# SparkFun_ACS712_Breakout_v11.net
KiCad netlist of a schematic drawn in EAGLE
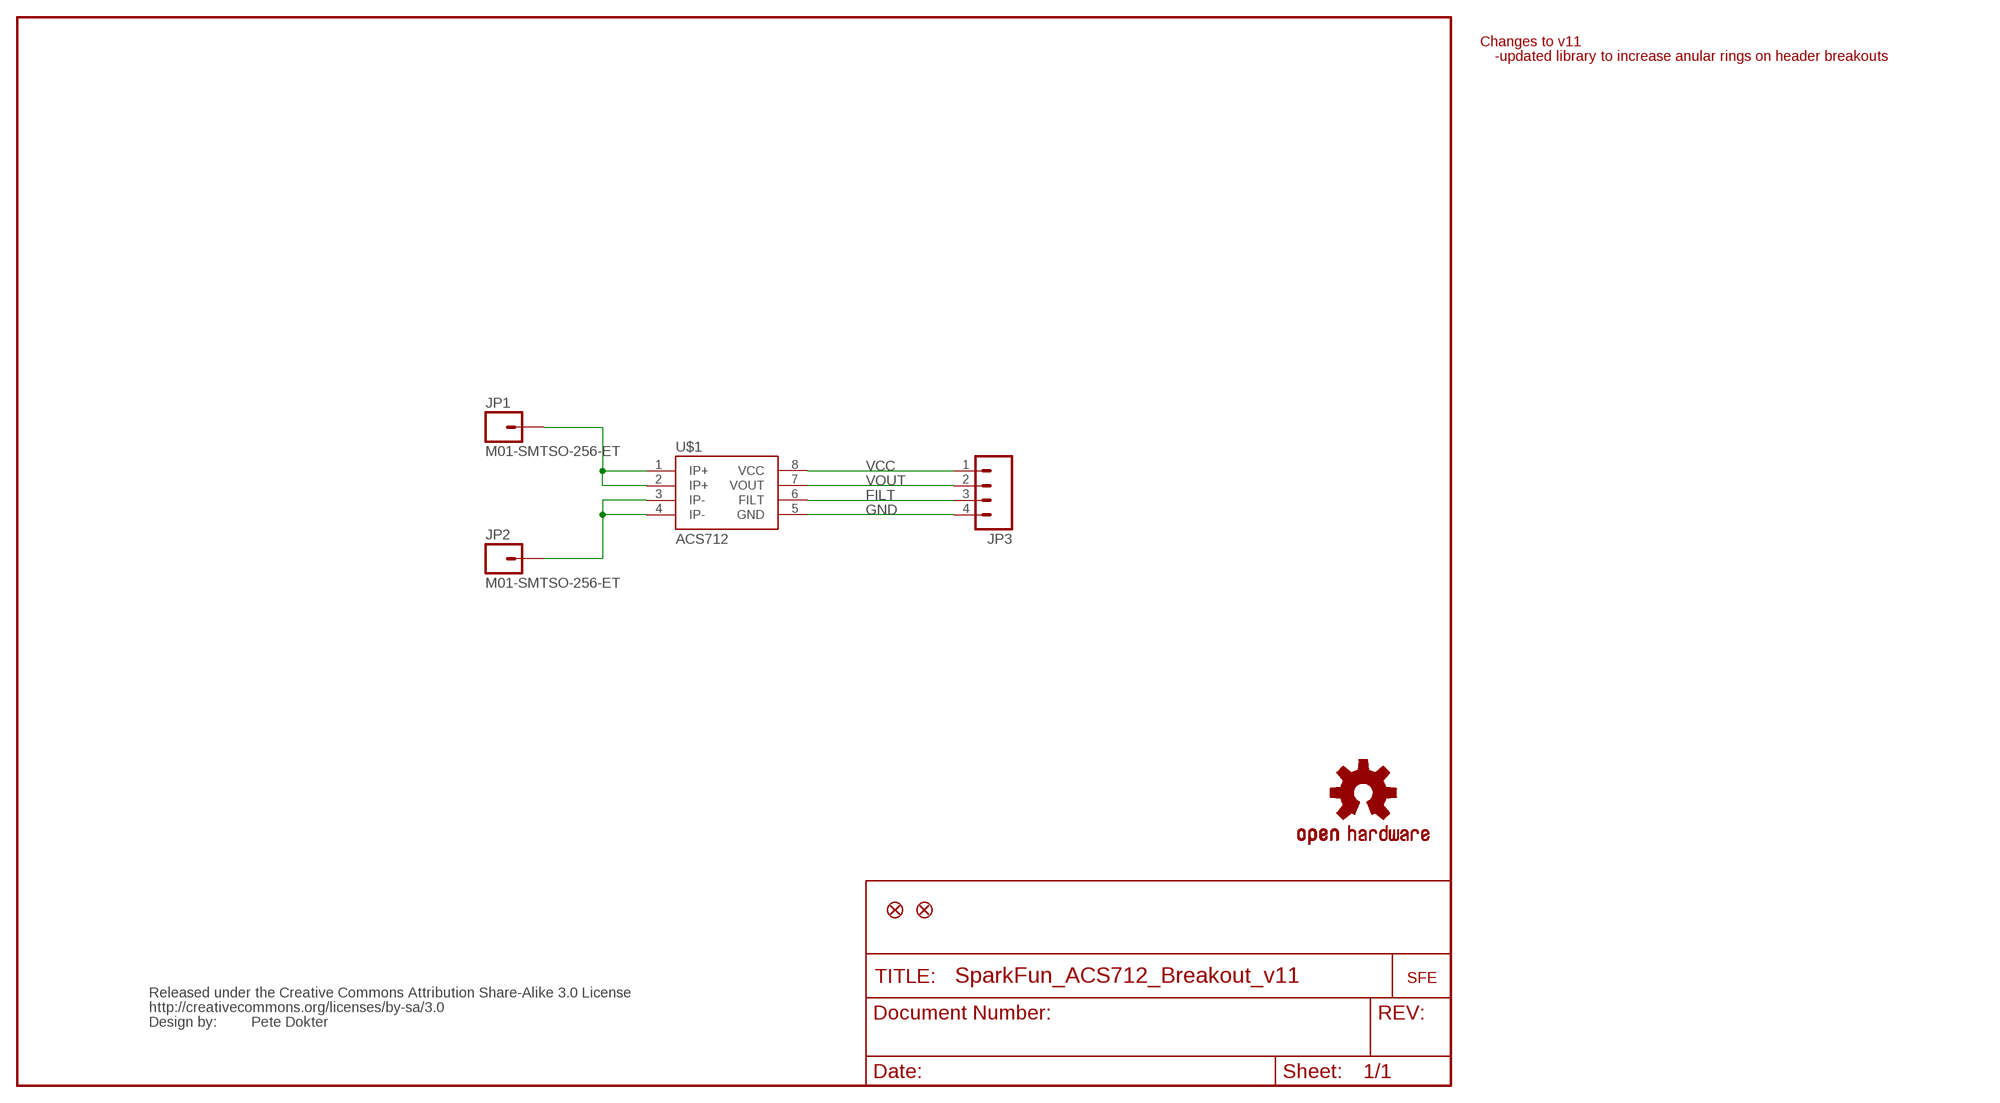
[diagram p0: schematic, sheet 1]

(export (version "E")
  (design (tool "Eeschema 10.0.6"))
  (components
    (comp (ref "JP1")
      (value "M01-SMTSO-256-ET")
      (footprint "eagle-import:SMTSO-256-ET")
      (libsource (lib "eagle-import") (part "M01-SMTSO-256-ET"))
    )
    (comp (ref "JP2")
      (value "M01-SMTSO-256-ET")
      (footprint "eagle-import:SMTSO-256-ET")
      (libsource (lib "eagle-import") (part "M01-SMTSO-256-ET"))
    )
    (comp (ref "JP3")
      (value "M04PTH")
      (footprint "eagle-import:1X04")
      (libsource (lib "eagle-import") (part "M04PTH"))
    )
    (comp (ref "JP4")
      (value "FIDUCIALUFIDUCIAL")
      (footprint "eagle-import:MICRO-FIDUCIAL")
      (libsource (lib "eagle-import") (part "FIDUCIALUFIDUCIAL"))
    )
    (comp (ref "JP5")
      (value "FIDUCIALUFIDUCIAL")
      (footprint "eagle-import:MICRO-FIDUCIAL")
      (libsource (lib "eagle-import") (part "FIDUCIALUFIDUCIAL"))
    )
    (comp (ref "U$1")
      (value "ACS712")
      (footprint "eagle-import:SO08")
      (libsource (lib "eagle-import") (part "ACS712"))
    )
    (comp (ref "U$2")
      (value "LOGO-FLAME-LARGE")
      (footprint "eagle-import:LOGO-FLAME-LARGE")
      (libsource (lib "eagle-import") (part "LOGO-FLAME-LARGE"))
    )
    (comp (ref "U$3")
      (value "OSHW-LOGOS")
      (footprint "eagle-import:OSHW-LOGO-S")
      (libsource (lib "eagle-import") (part "OSHW-LOGOS"))
    )
    (comp (ref "U$4")
      (value "CREATIVE_COMMONS")
      (footprint "eagle-import:CREATIVE_COMMONS")
      (libsource (lib "eagle-import") (part "CREATIVE_COMMONS"))
    )
  )
  (nets
    (net (code "1") (name "/FILT") (class "Default")
      (node (ref "JP3") (pin "3") (pinfunction "3_3") (pintype "passive"))
      (node (ref "U$1") (pin "6") (pinfunction "FILT_6") (pintype "bidirectional"))
    )
    (net (code "2") (name "/GND") (class "Default")
      (node (ref "JP3") (pin "4") (pinfunction "4_4") (pintype "passive"))
      (node (ref "U$1") (pin "5") (pinfunction "GND_5") (pintype "bidirectional"))
    )
    (net (code "3") (name "/VCC") (class "Default")
      (node (ref "JP3") (pin "1") (pinfunction "1_1") (pintype "passive"))
      (node (ref "U$1") (pin "8") (pinfunction "VCC_8") (pintype "bidirectional"))
    )
    (net (code "4") (name "/VOUT") (class "Default")
      (node (ref "JP3") (pin "2") (pinfunction "2_2") (pintype "passive"))
      (node (ref "U$1") (pin "7") (pinfunction "VOUT_7") (pintype "bidirectional"))
    )
    (net (code "5") (name "Net-(JP1-1)") (class "Default")
      (node (ref "JP1") (pin "P$1") (pinfunction "1_P$1") (pintype "passive"))
      (node (ref "U$1") (pin "1") (pinfunction "IP+_1") (pintype "bidirectional"))
      (node (ref "U$1") (pin "2") (pinfunction "IP+_2") (pintype "bidirectional"))
    )
    (net (code "6") (name "Net-(JP2-1)") (class "Default")
      (node (ref "JP2") (pin "P$1") (pinfunction "1_P$1") (pintype "passive"))
      (node (ref "U$1") (pin "3") (pinfunction "IP-_3") (pintype "bidirectional"))
      (node (ref "U$1") (pin "4") (pinfunction "IP-_4") (pintype "bidirectional"))
    )
  )
)
